# SCH_PieV2.net
KiCad netlist of a schematic drawn in EasyEDA
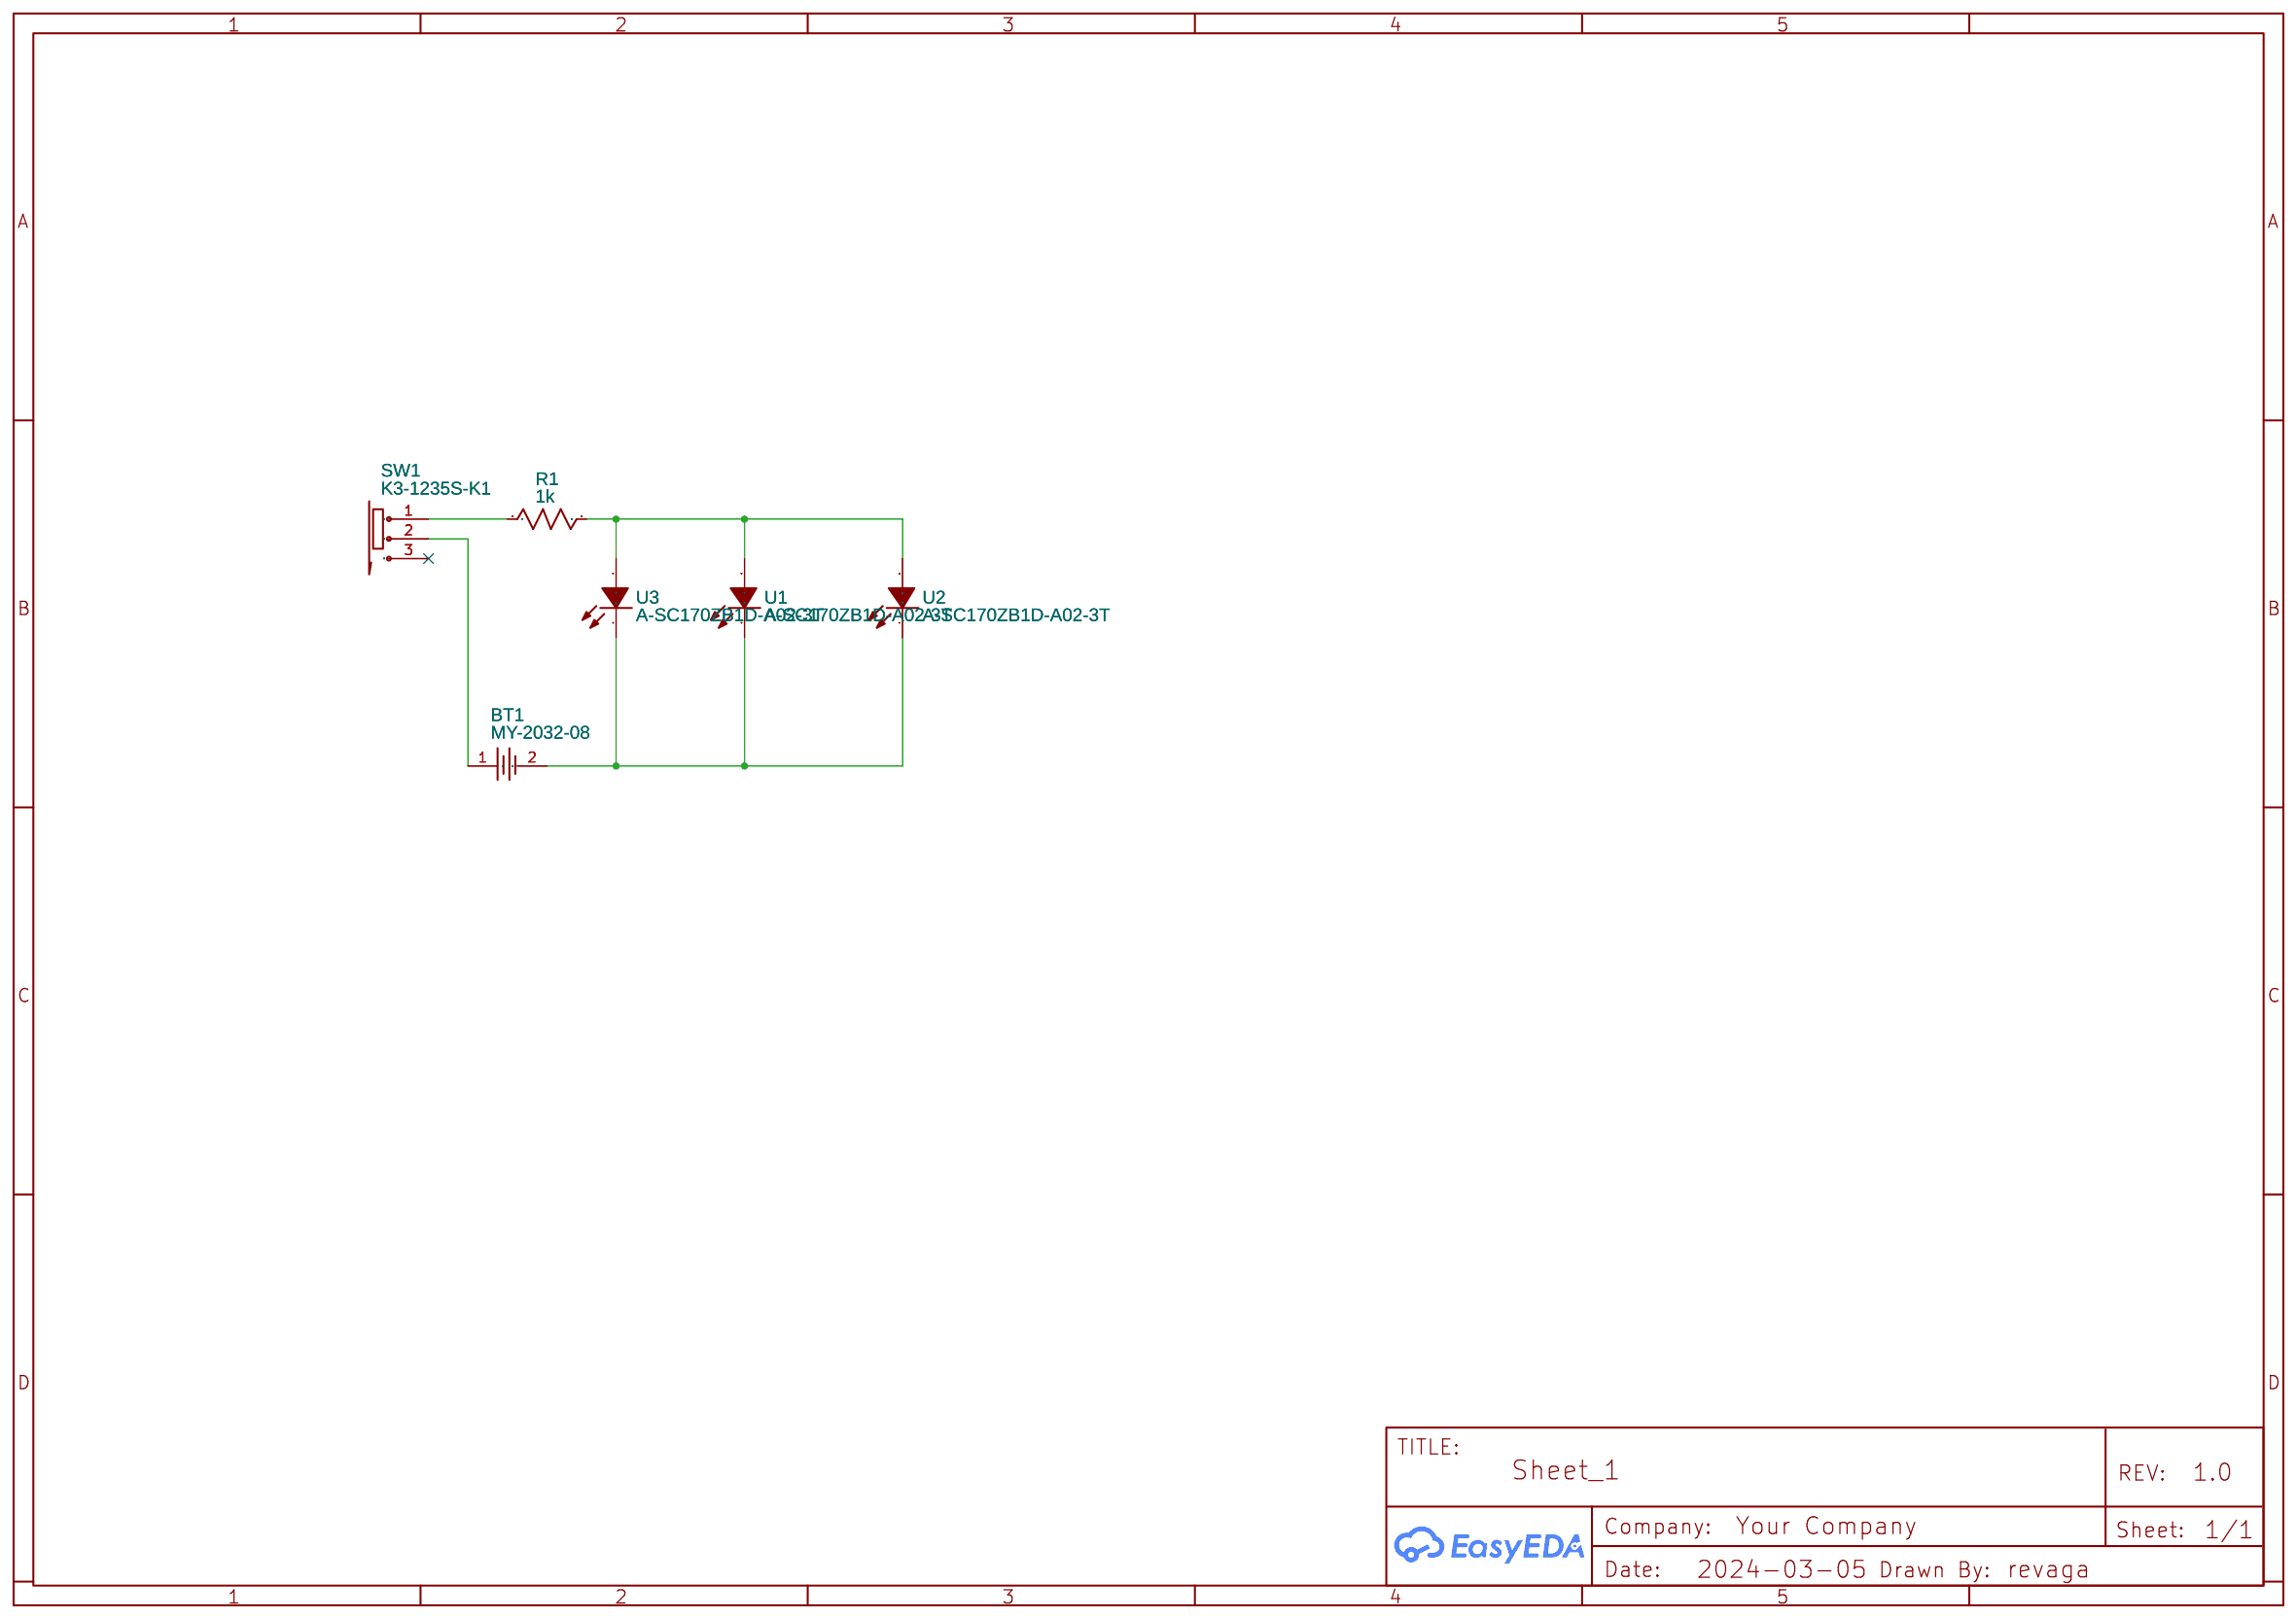
[diagram p0: schematic sheet]

(export (version "E")
  (design (tool "Eeschema 10.0.6"))
  (components
    (comp (ref "BT1")
      (value "MY-2032-08")
      (fields (field (name "Manufacturer") "MYOUNG(美阳)"))
      (libsource (lib "") (part "MY-2032-08"))
    )
    (comp (ref "R1") (value "1k") (libsource (lib "") (part "R_0402_US")))
    (comp (ref "SW1")
      (value "K3-1235S-K1")
      (fields (field (name "Manufacturer") "韩国韩荣"))
      (libsource (lib "") (part "K3-1235S-K1"))
    )
    (comp (ref "U1")
      (value "A-SC170ZB1D-A02-3T")
      (fields (field (name "Manufacturer") "Amicc(欧密格光电)"))
      (libsource (lib "") (part "A-SC170ZB1D-A02-3T"))
    )
    (comp (ref "U2")
      (value "A-SC170ZB1D-A02-3T")
      (fields (field (name "Manufacturer") "Amicc(欧密格光电)"))
      (libsource (lib "") (part "A-SC170ZB1D-A02-3T"))
    )
    (comp (ref "U3")
      (value "A-SC170ZB1D-A02-3T")
      (fields (field (name "Manufacturer") "Amicc(欧密格光电)"))
      (libsource (lib "") (part "A-SC170ZB1D-A02-3T"))
    )
  )
  (nets
    (net (code "1") (name "Net-(BT1-Pad1)") (class "Default")
      (node (ref "BT1") (pin "1") (pinfunction "1_1") (pintype "input"))
      (node (ref "SW1") (pin "2") (pinfunction "2_2") (pintype "unspecified"))
    )
    (net (code "2") (name "Net-(R1-Pad1)") (class "Default")
      (node (ref "R1") (pin "1") (pinfunction "1_1") (pintype "unspecified"))
      (node (ref "SW1") (pin "1") (pinfunction "1_1") (pintype "unspecified"))
    )
    (net (code "3") (name "Net-(U1-A)") (class "Default")
      (node (ref "R1") (pin "2") (pinfunction "2_2") (pintype "unspecified"))
      (node (ref "U1") (pin "2") (pinfunction "A_2") (pintype "unspecified"))
      (node (ref "U2") (pin "2") (pinfunction "A_2") (pintype "unspecified"))
      (node (ref "U3") (pin "2") (pinfunction "A_2") (pintype "unspecified"))
    )
    (net (code "4") (name "Net-(U1-C)") (class "Default")
      (node (ref "BT1") (pin "2") (pinfunction "2_2") (pintype "input"))
      (node (ref "U1") (pin "1") (pinfunction "C_1") (pintype "unspecified"))
      (node (ref "U2") (pin "1") (pinfunction "C_1") (pintype "unspecified"))
      (node (ref "U3") (pin "1") (pinfunction "C_1") (pintype "unspecified"))
    )
    (net (code "5") (name "unconnected-(SW1-Pad3)") (class "Default")
      (node (ref "SW1") (pin "3") (pinfunction "3_3") (pintype "unspecified+no_connect"))
    )
  )
)
